# psoc.net
KiCad netlist of a schematic drawn in Altium Designer
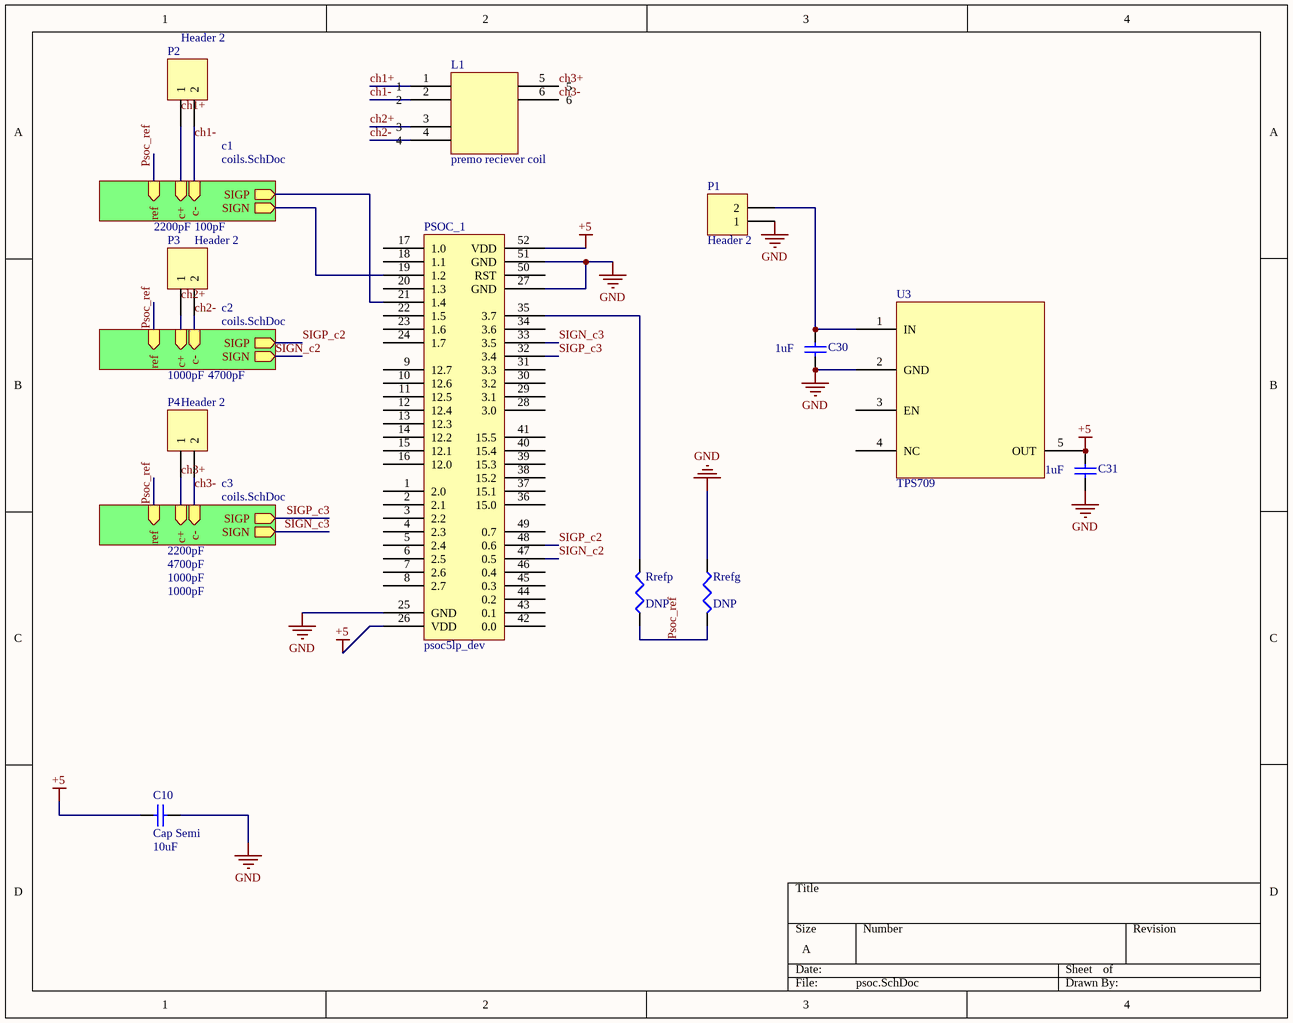
[diagram p0: psoc.SchDoc]

(export (version "E")
  (design (tool "Eeschema 10.0.6"))
  (components
    (comp (ref "C10")
      (value "Cap Semi")
      (footprint "1608[0603]")
      (description "Capacitor (Semiconductor SIM Model)")
      (fields (field (name "ALTIUM_VALUE") "10uF") (field (name "PUBLISHER") "Altium Limited"))
      (libsource (lib "Miscellaneous Devices") (part "Cap Semi"))
    )
    (comp (ref "C30")
      (value "1uF")
      (footprint "1608[0603]")
      (description "Capacitor (Semiconductor SIM Model)")
      (fields (field (name "PUBLISHER") "Altium Limited"))
      (libsource (lib "Miscellaneous Devices") (part "Cap Semi"))
    )
    (comp (ref "C31")
      (value "1uF")
      (footprint "1608[0603]")
      (description "Capacitor (Semiconductor SIM Model)")
      (fields (field (name "PUBLISHER") "Altium Limited"))
      (libsource (lib "Miscellaneous Devices") (part "Cap Semi"))
    )
    (comp (ref "L1")
      (value "premo reciever coil")
      (footprint "3DCC08-A")
      (libsource (lib "farshid") (part "premo reciever coil"))
    )
    (comp (ref "P1")
      (value "Header 2")
      (footprint "HDR1X2")
      (description "Header, 2-Pin")
      (fields (field (name "PUBLISHER") "Altium Limited"))
      (libsource (lib "") (part "Header 2_1"))
    )
    (comp (ref "P2")
      (value "Header 2")
      (footprint "HDR1X2")
      (description "Header, 2-Pin")
      (fields (field (name "PUBLISHER") "Altium Limited"))
      (libsource (lib "Miscellaneous Connectors") (part "Header 2"))
    )
    (comp (ref "P3")
      (value "Header 2")
      (footprint "HDR1X2")
      (description "Header, 2-Pin")
      (fields (field (name "PUBLISHER") "Altium Limited"))
      (libsource (lib "Miscellaneous Connectors") (part "Header 2"))
    )
    (comp (ref "P4")
      (value "Header 2")
      (footprint "HDR1X2")
      (description "Header, 2-Pin")
      (fields (field (name "PUBLISHER") "Altium Limited"))
      (libsource (lib "Miscellaneous Connectors") (part "Header 2"))
    )
    (comp (ref "PSOC_1")
      (value "psoc5lp_dev")
      (footprint "psoc:psoc5lp_devkit")
      (libsource (lib "psoc") (part "psoc5lp_dev"))
    )
    (comp (ref "Rrefg")
      (value "DNP")
      (footprint "J1-0603")
      (description "Resistor")
      (fields (field (name "PUBLISHER") "Altium Limited"))
      (libsource (lib "Miscellaneous Devices") (part "Res3"))
    )
    (comp (ref "Rrefp")
      (value "DNP")
      (footprint "J1-0603")
      (description "Resistor")
      (fields (field (name "PUBLISHER") "Altium Limited"))
      (libsource (lib "Miscellaneous Devices") (part "Res3"))
    )
    (comp (ref "U3")
      (value "TPS709")
      (footprint "SOT95P280X145-5N")
      (description "Ultra low power Voltage Regulator")
      (libsource (lib "Fromm") (part "TPS709"))
    )
  )
  (nets
    (net (code "1") (name "+5") (class "Default")
      (node (ref "C10") (pin "1") (pinfunction "1_1") (pintype "passive"))
      (node (ref "C31") (pin "1") (pinfunction "1_1") (pintype "passive"))
      (node (ref "PSOC_1") (pin "26") (pinfunction "VDD_26") (pintype "power_in"))
      (node (ref "PSOC_1") (pin "52") (pinfunction "VDD_52") (pintype "power_in"))
      (node (ref "U3") (pin "5") (pinfunction "OUT_5") (pintype "passive"))
    )
    (net (code "2") (name "/Psoc_ref") (class "Default")
      (node (ref "Rrefg") (pin "2") (pinfunction "2_2") (pintype "passive"))
      (node (ref "Rrefp") (pin "1") (pinfunction "1_1") (pintype "passive"))
    )
    (net (code "3") (name "/SIGN") (class "Default")
      (node (ref "PSOC_1") (pin "19") (pinfunction "1.2_19") (pintype "passive"))
    )
    (net (code "4") (name "/SIGN_c2") (class "Default")
      (node (ref "PSOC_1") (pin "47") (pinfunction "0.5_47") (pintype "passive"))
    )
    (net (code "5") (name "/SIGN_c3") (class "Default")
      (node (ref "PSOC_1") (pin "33") (pinfunction "3.5_33") (pintype "passive"))
    )
    (net (code "6") (name "/SIGP") (class "Default")
      (node (ref "PSOC_1") (pin "21") (pinfunction "1.4_21") (pintype "passive"))
    )
    (net (code "7") (name "/SIGP_c2") (class "Default")
      (node (ref "PSOC_1") (pin "48") (pinfunction "0.6_48") (pintype "passive"))
    )
    (net (code "8") (name "/SIGP_c3") (class "Default")
      (node (ref "PSOC_1") (pin "32") (pinfunction "3.4_32") (pintype "passive"))
    )
    (net (code "9") (name "/c+") (class "Default")
      (node (ref "P2") (pin "1") (pinfunction "1_1") (pintype "passive"))
    )
    (net (code "10") (name "/c+_1") (class "Default")
      (node (ref "P3") (pin "1") (pinfunction "1_1") (pintype "passive"))
    )
    (net (code "12") (name "/ch1-") (class "Default")
      (node (ref "P2") (pin "2") (pinfunction "2_2") (pintype "passive"))
    )
    (net (code "14") (name "/ch2-") (class "Default")
      (node (ref "P3") (pin "2") (pinfunction "2_2") (pintype "passive"))
    )
    (net (code "15") (name "/ch3+") (class "Default")
      (node (ref "P4") (pin "1") (pinfunction "1_1") (pintype "passive"))
    )
    (net (code "16") (name "/ch3-") (class "Default")
      (node (ref "P4") (pin "2") (pinfunction "2_2") (pintype "passive"))
    )
    (net (code "17") (name "GND") (class "Default")
      (node (ref "C10") (pin "2") (pinfunction "2_2") (pintype "passive"))
      (node (ref "C30") (pin "2") (pinfunction "2_2") (pintype "passive"))
      (node (ref "C31") (pin "2") (pinfunction "2_2") (pintype "passive"))
      (node (ref "P1") (pin "1") (pinfunction "1_1") (pintype "passive"))
      (node (ref "PSOC_1") (pin "25") (pinfunction "GND_25") (pintype "power_in"))
      (node (ref "PSOC_1") (pin "27") (pinfunction "GND_27") (pintype "power_in"))
      (node (ref "PSOC_1") (pin "51") (pinfunction "GND_51") (pintype "power_in"))
      (node (ref "Rrefg") (pin "1") (pinfunction "1_1") (pintype "passive"))
      (node (ref "U3") (pin "2") (pinfunction "GND_2") (pintype "passive"))
    )
    (net (code "18") (name "Net-(PSOC_1-3.7)") (class "Default")
      (node (ref "PSOC_1") (pin "35") (pinfunction "3.7_35") (pintype "passive"))
      (node (ref "Rrefp") (pin "2") (pinfunction "2_2") (pintype "passive"))
    )
    (net (code "19") (name "Net-(U3-IN)") (class "Default")
      (node (ref "C30") (pin "1") (pinfunction "1_1") (pintype "passive"))
      (node (ref "P1") (pin "2") (pinfunction "2_2") (pintype "passive"))
      (node (ref "U3") (pin "1") (pinfunction "IN_1") (pintype "passive"))
    )
    (net (code "20") (name "unconnected-(L1-Pad1)") (class "Default")
      (node (ref "L1") (pin "1") (pinfunction "1_1") (pintype "passive"))
    )
    (net (code "21") (name "unconnected-(L1-Pad2)") (class "Default")
      (node (ref "L1") (pin "2") (pinfunction "2_2") (pintype "passive"))
    )
    (net (code "22") (name "unconnected-(L1-Pad3)") (class "Default")
      (node (ref "L1") (pin "3") (pinfunction "3_3") (pintype "passive"))
    )
    (net (code "23") (name "unconnected-(L1-Pad4)") (class "Default")
      (node (ref "L1") (pin "4") (pinfunction "4_4") (pintype "passive"))
    )
    (net (code "24") (name "unconnected-(L1-Pad5)") (class "Default")
      (node (ref "L1") (pin "5") (pinfunction "5_5") (pintype "passive"))
    )
    (net (code "25") (name "unconnected-(L1-Pad6)") (class "Default")
      (node (ref "L1") (pin "6") (pinfunction "6_6") (pintype "passive"))
    )
    (net (code "26") (name "unconnected-(PSOC_1-0.0-Pad42)") (class "Default")
      (node (ref "PSOC_1") (pin "42") (pinfunction "0.0_42") (pintype "passive"))
    )
    (net (code "27") (name "unconnected-(PSOC_1-0.1-Pad43)") (class "Default")
      (node (ref "PSOC_1") (pin "43") (pinfunction "0.1_43") (pintype "passive"))
    )
    (net (code "28") (name "unconnected-(PSOC_1-0.2-Pad44)") (class "Default")
      (node (ref "PSOC_1") (pin "44") (pinfunction "0.2_44") (pintype "passive"))
    )
    (net (code "29") (name "unconnected-(PSOC_1-0.3-Pad45)") (class "Default")
      (node (ref "PSOC_1") (pin "45") (pinfunction "0.3_45") (pintype "passive"))
    )
    (net (code "30") (name "unconnected-(PSOC_1-0.4-Pad46)") (class "Default")
      (node (ref "PSOC_1") (pin "46") (pinfunction "0.4_46") (pintype "passive"))
    )
    (net (code "31") (name "unconnected-(PSOC_1-0.7-Pad49)") (class "Default")
      (node (ref "PSOC_1") (pin "49") (pinfunction "0.7_49") (pintype "passive"))
    )
    (net (code "32") (name "unconnected-(PSOC_1-1.0-Pad17)") (class "Default")
      (node (ref "PSOC_1") (pin "17") (pinfunction "1.0_17") (pintype "passive"))
    )
    (net (code "33") (name "unconnected-(PSOC_1-1.1-Pad18)") (class "Default")
      (node (ref "PSOC_1") (pin "18") (pinfunction "1.1_18") (pintype "passive"))
    )
    (net (code "34") (name "unconnected-(PSOC_1-1.3-Pad20)") (class "Default")
      (node (ref "PSOC_1") (pin "20") (pinfunction "1.3_20") (pintype "passive"))
    )
    (net (code "35") (name "unconnected-(PSOC_1-1.5-Pad22)") (class "Default")
      (node (ref "PSOC_1") (pin "22") (pinfunction "1.5_22") (pintype "passive"))
    )
    (net (code "36") (name "unconnected-(PSOC_1-1.6-Pad23)") (class "Default")
      (node (ref "PSOC_1") (pin "23") (pinfunction "1.6_23") (pintype "passive"))
    )
    (net (code "37") (name "unconnected-(PSOC_1-1.7-Pad24)") (class "Default")
      (node (ref "PSOC_1") (pin "24") (pinfunction "1.7_24") (pintype "passive"))
    )
    (net (code "38") (name "unconnected-(PSOC_1-2.0-Pad1)") (class "Default")
      (node (ref "PSOC_1") (pin "1") (pinfunction "2.0_1") (pintype "passive"))
    )
    (net (code "39") (name "unconnected-(PSOC_1-2.1-Pad2)") (class "Default")
      (node (ref "PSOC_1") (pin "2") (pinfunction "2.1_2") (pintype "passive"))
    )
    (net (code "40") (name "unconnected-(PSOC_1-2.2-Pad3)") (class "Default")
      (node (ref "PSOC_1") (pin "3") (pinfunction "2.2_3") (pintype "passive"))
    )
    (net (code "41") (name "unconnected-(PSOC_1-2.3-Pad4)") (class "Default")
      (node (ref "PSOC_1") (pin "4") (pinfunction "2.3_4") (pintype "passive"))
    )
    (net (code "42") (name "unconnected-(PSOC_1-2.4-Pad5)") (class "Default")
      (node (ref "PSOC_1") (pin "5") (pinfunction "2.4_5") (pintype "passive"))
    )
    (net (code "43") (name "unconnected-(PSOC_1-2.5-Pad6)") (class "Default")
      (node (ref "PSOC_1") (pin "6") (pinfunction "2.5_6") (pintype "passive"))
    )
    (net (code "44") (name "unconnected-(PSOC_1-2.6-Pad7)") (class "Default")
      (node (ref "PSOC_1") (pin "7") (pinfunction "2.6_7") (pintype "passive"))
    )
    (net (code "45") (name "unconnected-(PSOC_1-2.7-Pad8)") (class "Default")
      (node (ref "PSOC_1") (pin "8") (pinfunction "2.7_8") (pintype "passive"))
    )
    (net (code "46") (name "unconnected-(PSOC_1-3.0-Pad28)") (class "Default")
      (node (ref "PSOC_1") (pin "28") (pinfunction "3.0_28") (pintype "passive"))
    )
    (net (code "47") (name "unconnected-(PSOC_1-3.1-Pad29)") (class "Default")
      (node (ref "PSOC_1") (pin "29") (pinfunction "3.1_29") (pintype "passive"))
    )
    (net (code "48") (name "unconnected-(PSOC_1-3.2-Pad30)") (class "Default")
      (node (ref "PSOC_1") (pin "30") (pinfunction "3.2_30") (pintype "passive"))
    )
    (net (code "49") (name "unconnected-(PSOC_1-3.3-Pad31)") (class "Default")
      (node (ref "PSOC_1") (pin "31") (pinfunction "3.3_31") (pintype "passive"))
    )
    (net (code "50") (name "unconnected-(PSOC_1-3.6-Pad34)") (class "Default")
      (node (ref "PSOC_1") (pin "34") (pinfunction "3.6_34") (pintype "passive"))
    )
    (net (code "51") (name "unconnected-(PSOC_1-12.0-Pad16)") (class "Default")
      (node (ref "PSOC_1") (pin "16") (pinfunction "12.0_16") (pintype "passive"))
    )
    (net (code "52") (name "unconnected-(PSOC_1-12.1-Pad15)") (class "Default")
      (node (ref "PSOC_1") (pin "15") (pinfunction "12.1_15") (pintype "passive"))
    )
    (net (code "53") (name "unconnected-(PSOC_1-12.2-Pad14)") (class "Default")
      (node (ref "PSOC_1") (pin "14") (pinfunction "12.2_14") (pintype "passive"))
    )
    (net (code "54") (name "unconnected-(PSOC_1-12.3-Pad13)") (class "Default")
      (node (ref "PSOC_1") (pin "13") (pinfunction "12.3_13") (pintype "passive"))
    )
    (net (code "55") (name "unconnected-(PSOC_1-12.4-Pad12)") (class "Default")
      (node (ref "PSOC_1") (pin "12") (pinfunction "12.4_12") (pintype "passive"))
    )
    (net (code "56") (name "unconnected-(PSOC_1-12.5-Pad11)") (class "Default")
      (node (ref "PSOC_1") (pin "11") (pinfunction "12.5_11") (pintype "passive"))
    )
    (net (code "57") (name "unconnected-(PSOC_1-12.6-Pad10)") (class "Default")
      (node (ref "PSOC_1") (pin "10") (pinfunction "12.6_10") (pintype "passive"))
    )
    (net (code "58") (name "unconnected-(PSOC_1-12.7-Pad9)") (class "Default")
      (node (ref "PSOC_1") (pin "9") (pinfunction "12.7_9") (pintype "passive"))
    )
    (net (code "59") (name "unconnected-(PSOC_1-15.0-Pad36)") (class "Default")
      (node (ref "PSOC_1") (pin "36") (pinfunction "15.0_36") (pintype "passive"))
    )
    (net (code "60") (name "unconnected-(PSOC_1-15.1-Pad37)") (class "Default")
      (node (ref "PSOC_1") (pin "37") (pinfunction "15.1_37") (pintype "passive"))
    )
    (net (code "61") (name "unconnected-(PSOC_1-15.2-Pad38)") (class "Default")
      (node (ref "PSOC_1") (pin "38") (pinfunction "15.2_38") (pintype "passive"))
    )
    (net (code "62") (name "unconnected-(PSOC_1-15.3-Pad39)") (class "Default")
      (node (ref "PSOC_1") (pin "39") (pinfunction "15.3_39") (pintype "passive"))
    )
    (net (code "63") (name "unconnected-(PSOC_1-15.4-Pad40)") (class "Default")
      (node (ref "PSOC_1") (pin "40") (pinfunction "15.4_40") (pintype "passive"))
    )
    (net (code "64") (name "unconnected-(PSOC_1-15.5-Pad41)") (class "Default")
      (node (ref "PSOC_1") (pin "41") (pinfunction "15.5_41") (pintype "passive"))
    )
    (net (code "65") (name "unconnected-(PSOC_1-RST-Pad50)") (class "Default")
      (node (ref "PSOC_1") (pin "50") (pinfunction "RST_50") (pintype "power_in"))
    )
    (net (code "66") (name "unconnected-(U3-EN-Pad3)") (class "Default")
      (node (ref "U3") (pin "3") (pinfunction "EN_3") (pintype "passive"))
    )
    (net (code "67") (name "unconnected-(U3-NC-Pad4)") (class "Default")
      (node (ref "U3") (pin "4") (pinfunction "NC_4") (pintype "passive"))
    )
  )
)
